# main_board.net
KiCad netlist of a schematic drawn in EAGLE
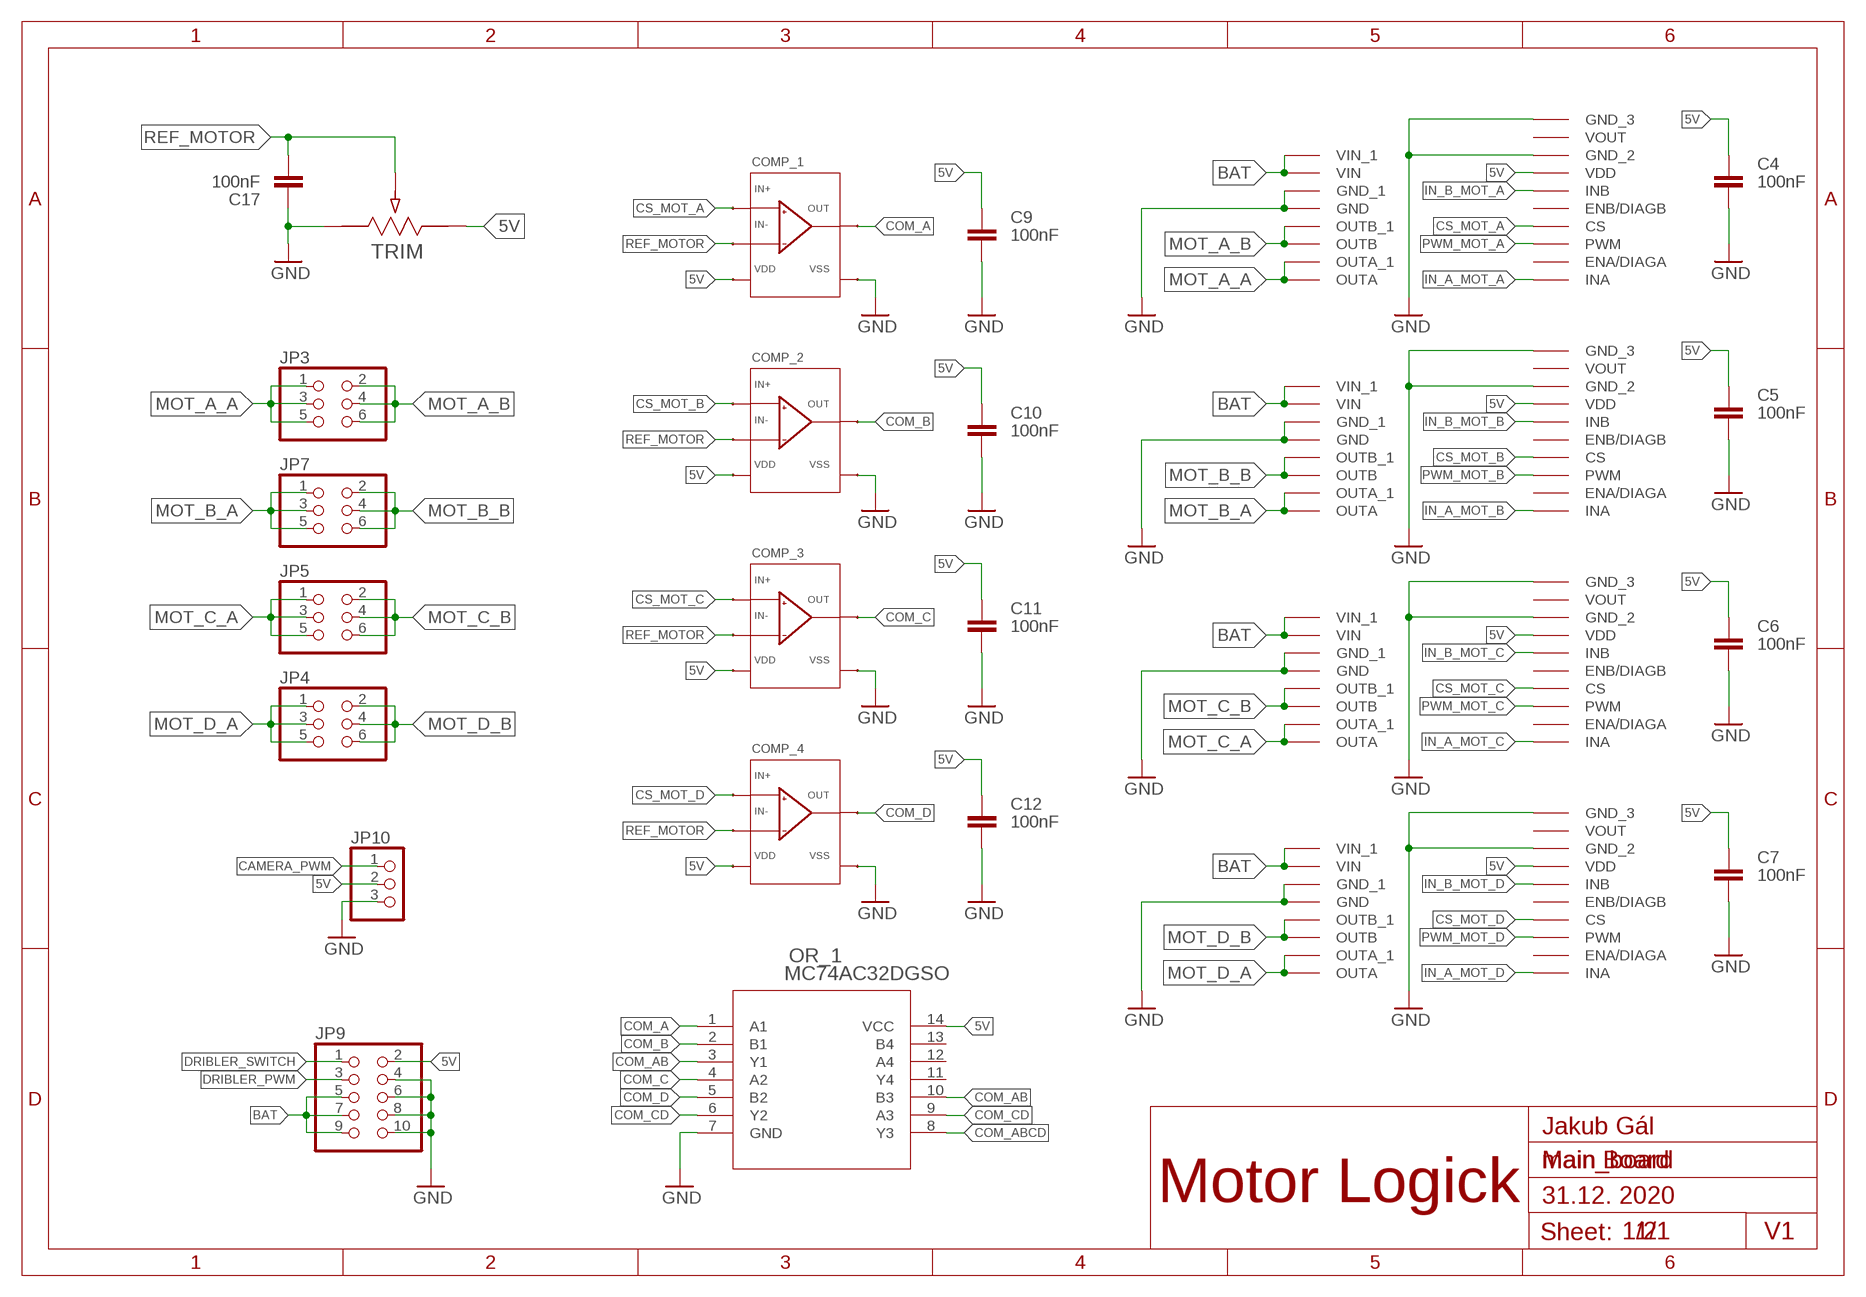
[diagram p0: schematic, sheet 1, part 1 of 2]
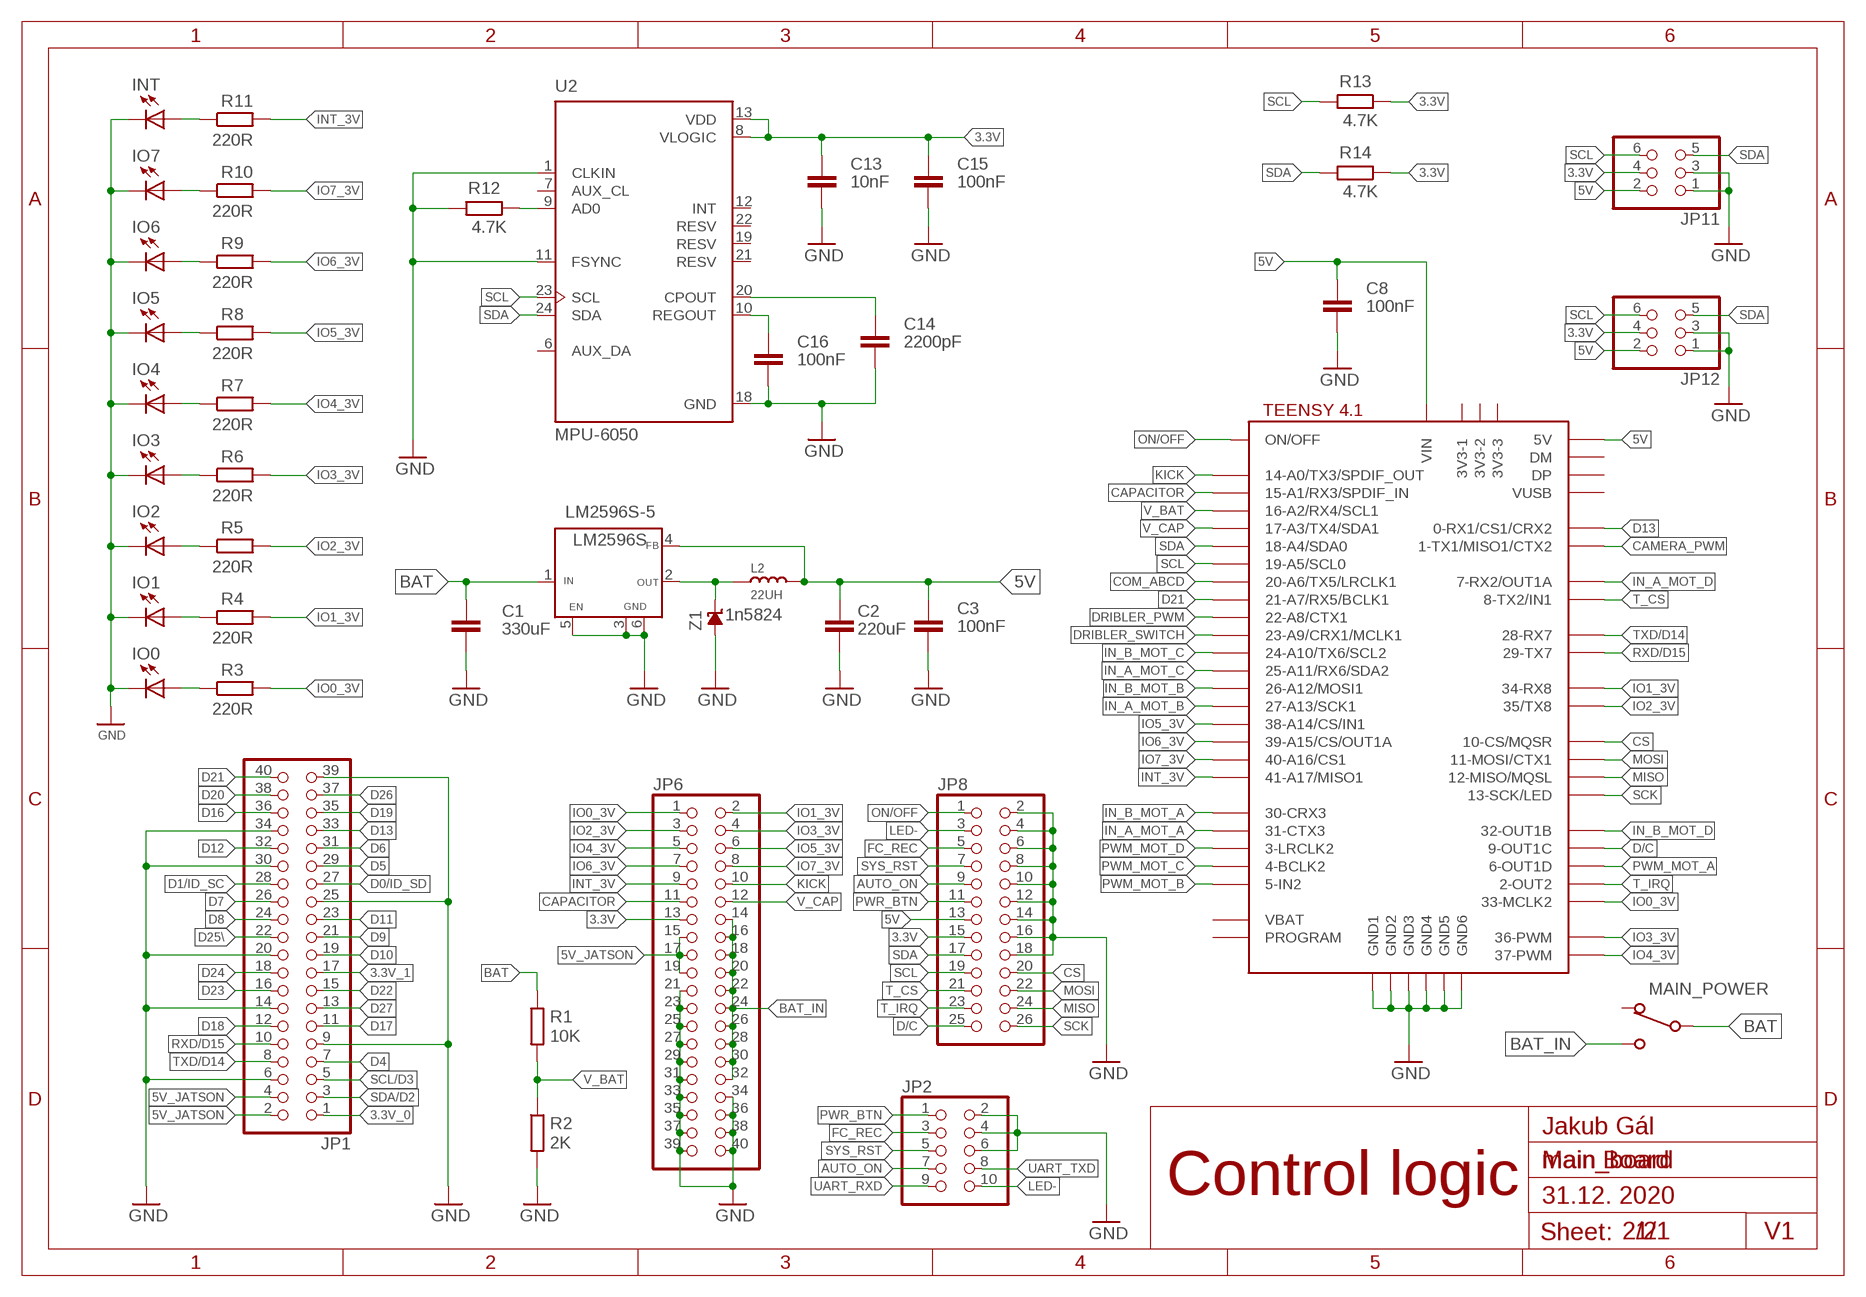
[diagram p1: schematic, sheet 1, part 2 of 2]

(export (version "E")
  (design (tool "Eeschema 10.0.6"))
  (components
    (comp (ref "C1")
      (value "330uF")
      (footprint "eagle-import:CAPM7343X310")
      (libsource (lib "eagle-import") (part "CTANTALUM-2917(7343-METRIC)_"))
    )
    (comp (ref "C2")
      (value "220uF")
      (footprint "eagle-import:CAPM7343X310")
      (libsource (lib "eagle-import") (part "CTANTALUM-2917(7343-METRIC)_"))
    )
    (comp (ref "C3")
      (value "100nF")
      (footprint "eagle-import:C0603")
      (libsource (lib "eagle-import") (part "C-EUC0603"))
    )
    (comp (ref "C4")
      (value "100nF")
      (footprint "eagle-import:C0603")
      (libsource (lib "eagle-import") (part "C-EUC0603"))
    )
    (comp (ref "C5")
      (value "100nF")
      (footprint "eagle-import:C0603")
      (libsource (lib "eagle-import") (part "C-EUC0603"))
    )
    (comp (ref "C6")
      (value "100nF")
      (footprint "eagle-import:C0603")
      (libsource (lib "eagle-import") (part "C-EUC0603"))
    )
    (comp (ref "C7")
      (value "100nF")
      (footprint "eagle-import:C0603")
      (libsource (lib "eagle-import") (part "C-EUC0603"))
    )
    (comp (ref "C8")
      (value "100nF")
      (footprint "eagle-import:C0603")
      (libsource (lib "eagle-import") (part "C-EUC0603"))
    )
    (comp (ref "C9")
      (value "100nF")
      (footprint "eagle-import:C0603")
      (libsource (lib "eagle-import") (part "C-EUC0603"))
    )
    (comp (ref "C10")
      (value "100nF")
      (footprint "eagle-import:C0603")
      (libsource (lib "eagle-import") (part "C-EUC0603"))
    )
    (comp (ref "C11")
      (value "100nF")
      (footprint "eagle-import:C0603")
      (libsource (lib "eagle-import") (part "C-EUC0603"))
    )
    (comp (ref "C12")
      (value "100nF")
      (footprint "eagle-import:C0603")
      (libsource (lib "eagle-import") (part "C-EUC0603"))
    )
    (comp (ref "C13")
      (value "10nF")
      (footprint "eagle-import:C0603")
      (libsource (lib "eagle-import") (part "C-EUC0603"))
    )
    (comp (ref "C14")
      (value "2200pF")
      (footprint "eagle-import:C0603")
      (libsource (lib "eagle-import") (part "C-EUC0603"))
    )
    (comp (ref "C15")
      (value "100nF")
      (footprint "eagle-import:C0603")
      (libsource (lib "eagle-import") (part "C-EUC0603"))
    )
    (comp (ref "C16")
      (value "100nF")
      (footprint "eagle-import:C0603")
      (libsource (lib "eagle-import") (part "C-EUC0603"))
    )
    (comp (ref "C17")
      (value "100nF")
      (footprint "eagle-import:C0603")
      (libsource (lib "eagle-import") (part "C-EUC0603"))
    )
    (comp (ref "COMP_1")
      (value "TC75S56FUTE85LF")
      (footprint "eagle-import:SOT-353___(USV)_TOS")
      (libsource (lib "eagle-import") (part "TC75S56FUTE85LF"))
    )
    (comp (ref "COMP_2")
      (value "TC75S56FUTE85LF")
      (footprint "eagle-import:SOT-353___(USV)_TOS")
      (libsource (lib "eagle-import") (part "TC75S56FUTE85LF"))
    )
    (comp (ref "COMP_3")
      (value "TC75S56FUTE85LF")
      (footprint "eagle-import:SOT-353___(USV)_TOS")
      (libsource (lib "eagle-import") (part "TC75S56FUTE85LF"))
    )
    (comp (ref "COMP_4")
      (value "TC75S56FUTE85LF")
      (footprint "eagle-import:SOT-353___(USV)_TOS")
      (libsource (lib "eagle-import") (part "TC75S56FUTE85LF"))
    )
    (comp (ref "DRIVER_A")
      (value "MOTOR_DRIVER")
      (footprint "eagle-import:MOTOR_DRIVER")
      (libsource (lib "eagle-import") (part "MOTOR_DRIVER"))
    )
    (comp (ref "DRIVER_B")
      (value "MOTOR_DRIVER")
      (footprint "eagle-import:MOTOR_DRIVER")
      (libsource (lib "eagle-import") (part "MOTOR_DRIVER"))
    )
    (comp (ref "DRIVER_C")
      (value "MOTOR_DRIVER")
      (footprint "eagle-import:MOTOR_DRIVER")
      (libsource (lib "eagle-import") (part "MOTOR_DRIVER"))
    )
    (comp (ref "DRIVER_D")
      (value "MOTOR_DRIVER")
      (footprint "eagle-import:MOTOR_DRIVER")
      (libsource (lib "eagle-import") (part "MOTOR_DRIVER"))
    )
    (comp (ref "INT")
      (value "LEDCHIPLED_0603")
      (footprint "eagle-import:CHIPLED_0603")
      (libsource (lib "eagle-import") (part "LEDCHIPLED_0603"))
    )
    (comp (ref "IO0")
      (value "LEDCHIPLED_0603")
      (footprint "eagle-import:CHIPLED_0603")
      (libsource (lib "eagle-import") (part "LEDCHIPLED_0603"))
    )
    (comp (ref "IO1")
      (value "LEDCHIPLED_0603")
      (footprint "eagle-import:CHIPLED_0603")
      (libsource (lib "eagle-import") (part "LEDCHIPLED_0603"))
    )
    (comp (ref "IO2")
      (value "LEDCHIPLED_0603")
      (footprint "eagle-import:CHIPLED_0603")
      (libsource (lib "eagle-import") (part "LEDCHIPLED_0603"))
    )
    (comp (ref "IO3")
      (value "LEDCHIPLED_0603")
      (footprint "eagle-import:CHIPLED_0603")
      (libsource (lib "eagle-import") (part "LEDCHIPLED_0603"))
    )
    (comp (ref "IO4")
      (value "LEDCHIPLED_0603")
      (footprint "eagle-import:CHIPLED_0603")
      (libsource (lib "eagle-import") (part "LEDCHIPLED_0603"))
    )
    (comp (ref "IO5")
      (value "LEDCHIPLED_0603")
      (footprint "eagle-import:CHIPLED_0603")
      (libsource (lib "eagle-import") (part "LEDCHIPLED_0603"))
    )
    (comp (ref "IO6")
      (value "LEDCHIPLED_0603")
      (footprint "eagle-import:CHIPLED_0603")
      (libsource (lib "eagle-import") (part "LEDCHIPLED_0603"))
    )
    (comp (ref "IO7")
      (value "LEDCHIPLED_0603")
      (footprint "eagle-import:CHIPLED_0603")
      (libsource (lib "eagle-import") (part "LEDCHIPLED_0603"))
    )
    (comp (ref "JP1")
      (value "PINHD-2X20_2.54-SMD")
      (footprint "eagle-import:2X20SMD")
      (libsource (lib "eagle-import") (part "PINHD-2X20_2.54-SMD"))
    )
    (comp (ref "JP2")
      (value "PINHD-2X5_2.54")
      (footprint "eagle-import:2X05")
      (libsource (lib "eagle-import") (part "PINHD-2X5_2.54"))
    )
    (comp (ref "JP3")
      (value "PINHD-2X3IDC")
      (footprint "eagle-import:2X03_IDC")
      (libsource (lib "eagle-import") (part "PINHD-2X3IDC"))
    )
    (comp (ref "JP4")
      (value "PINHD-2X3IDC")
      (footprint "eagle-import:2X03_IDC")
      (libsource (lib "eagle-import") (part "PINHD-2X3IDC"))
    )
    (comp (ref "JP5")
      (value "PINHD-2X3IDC")
      (footprint "eagle-import:2X03_IDC")
      (libsource (lib "eagle-import") (part "PINHD-2X3IDC"))
    )
    (comp (ref "JP6")
      (value "PINHD-2X20_2.54")
      (footprint "eagle-import:2X20")
      (libsource (lib "eagle-import") (part "PINHD-2X20_2.54"))
    )
    (comp (ref "JP7")
      (value "PINHD-2X3IDC")
      (footprint "eagle-import:2X03_IDC")
      (libsource (lib "eagle-import") (part "PINHD-2X3IDC"))
    )
    (comp (ref "JP8")
      (value "PINHD-2X13_2.54")
      (footprint "eagle-import:2X13")
      (libsource (lib "eagle-import") (part "PINHD-2X13_2.54"))
    )
    (comp (ref "JP9")
      (value "PINHD-2X5_2.54")
      (footprint "eagle-import:2X05")
      (libsource (lib "eagle-import") (part "PINHD-2X5_2.54"))
    )
    (comp (ref "JP10")
      (value "PINHD-1X3")
      (footprint "eagle-import:1X03")
      (libsource (lib "eagle-import") (part "PINHD-1X3"))
    )
    (comp (ref "JP11")
      (value "PINHD-2X3IDC")
      (footprint "eagle-import:2X03_IDC")
      (libsource (lib "eagle-import") (part "PINHD-2X3IDC"))
    )
    (comp (ref "JP12")
      (value "PINHD-2X3IDC")
      (footprint "eagle-import:2X03_IDC")
      (libsource (lib "eagle-import") (part "PINHD-2X3IDC"))
    )
    (comp (ref "L2")
      (value "22UH")
      (footprint "eagle-import:INDUCTOR_L0630")
      (libsource (lib "eagle-import") (part "INDUCTOR/FERRITE-BEAD0630"))
    )
    (comp (ref "LM2596S")
      (value "LM2596S-5")
      (footprint "eagle-import:TO263-5")
      (libsource (lib "eagle-import") (part "LM2596S"))
    )
    (comp (ref "MAIN_POWER")
      (value "PREP-1PB")
      (footprint "eagle-import:P-B069B")
      (libsource (lib "eagle-import") (part "PREP-1PB"))
    )
    (comp (ref "OR_1")
      (value "MC74AC32DGSO")
      (footprint "eagle-import:SOIC-14_NB_ONS-M")
      (fields
        (field (name "MANUFACTURER_PART_NUMBER") "MC74VHC32DR2G")
        (field (name "COPYRIGHT") "Copyright (C) 2016 Accelerated Designs. All rights reserved")
      )
      (libsource (lib "eagle-import") (part "MC74AC32DGSOIC-14_NB_ONS-M"))
    )
    (comp (ref "R1")
      (value "10K")
      (footprint "eagle-import:R0603")
      (libsource (lib "eagle-import") (part "R-EU_R0603"))
    )
    (comp (ref "R2")
      (value "2K")
      (footprint "eagle-import:R0603")
      (libsource (lib "eagle-import") (part "R-EU_R0603"))
    )
    (comp (ref "R3")
      (value "220R")
      (footprint "eagle-import:R0603")
      (libsource (lib "eagle-import") (part "R-EU_R0603"))
    )
    (comp (ref "R4")
      (value "220R")
      (footprint "eagle-import:R0603")
      (libsource (lib "eagle-import") (part "R-EU_R0603"))
    )
    (comp (ref "R5")
      (value "220R")
      (footprint "eagle-import:R0603")
      (libsource (lib "eagle-import") (part "R-EU_R0603"))
    )
    (comp (ref "R6")
      (value "220R")
      (footprint "eagle-import:R0603")
      (libsource (lib "eagle-import") (part "R-EU_R0603"))
    )
    (comp (ref "R7")
      (value "220R")
      (footprint "eagle-import:R0603")
      (libsource (lib "eagle-import") (part "R-EU_R0603"))
    )
    (comp (ref "R8")
      (value "220R")
      (footprint "eagle-import:R0603")
      (libsource (lib "eagle-import") (part "R-EU_R0603"))
    )
    (comp (ref "R9")
      (value "220R")
      (footprint "eagle-import:R0603")
      (libsource (lib "eagle-import") (part "R-EU_R0603"))
    )
    (comp (ref "R10")
      (value "220R")
      (footprint "eagle-import:R0603")
      (libsource (lib "eagle-import") (part "R-EU_R0603"))
    )
    (comp (ref "R11")
      (value "220R")
      (footprint "eagle-import:R0603")
      (libsource (lib "eagle-import") (part "R-EU_R0603"))
    )
    (comp (ref "R12")
      (value "4.7K")
      (footprint "eagle-import:R0603")
      (libsource (lib "eagle-import") (part "R-EU_R0603"))
    )
    (comp (ref "R13")
      (value "4.7K")
      (footprint "eagle-import:R0603")
      (libsource (lib "eagle-import") (part "R-EU_R0603"))
    )
    (comp (ref "R14")
      (value "4.7K")
      (footprint "eagle-import:R0603")
      (libsource (lib "eagle-import") (part "R-EU_R0603"))
    )
    (comp (ref "TEENSY41")
      (value "TEENSY41-E")
      (footprint "eagle-import:TENNSY41-E")
      (libsource (lib "eagle-import") (part "TEENSY41-E"))
    )
    (comp (ref "TRIM")
      (value "3362W-1-103LF")
      (footprint "eagle-import:POT_3362W")
      (libsource (lib "eagle-import") (part "3362W-1-103LF"))
    )
    (comp (ref "U2")
      (value "MPU-6050")
      (footprint "eagle-import:QFN50P400X400X95-24N")
      (fields (field (name "MF") "TDK InvenSense"))
      (libsource (lib "eagle-import") (part "MPU-6050"))
    )
    (comp (ref "Z1")
      (value "1n5824")
      (footprint "eagle-import:SUPRESSOR_SMAJ")
      (libsource (lib "eagle-import") (part "SUPRESSOR_TVS-UD-SMAJ"))
    )
  )
  (nets
    (net (code "1") (name "3.3V") (class "Default")
      (node (ref "C13") (pin "1") (pinfunction "1_1") (pintype "passive"))
      (node (ref "C15") (pin "1") (pinfunction "1_1") (pintype "passive"))
      (node (ref "JP11") (pin "4") (pinfunction "4_4") (pintype "passive"))
      (node (ref "JP12") (pin "4") (pinfunction "4_4") (pintype "passive"))
      (node (ref "JP6") (pin "13") (pinfunction "13_13") (pintype "passive"))
      (node (ref "JP8") (pin "15") (pinfunction "15_15") (pintype "passive"))
      (node (ref "R13") (pin "1") (pinfunction "1_1") (pintype "passive"))
      (node (ref "R14") (pin "1") (pinfunction "1_1") (pintype "passive"))
      (node (ref "U2") (pin "13") (pinfunction "VDD_13") (pintype "power_in"))
      (node (ref "U2") (pin "8") (pinfunction "VLOGIC_8") (pintype "power_in"))
    )
    (net (code "2") (name "3.3V_0") (class "Default")
      (node (ref "JP1") (pin "1") (pinfunction "1_1") (pintype "passive"))
    )
    (net (code "3") (name "3.3V_1") (class "Default")
      (node (ref "JP1") (pin "17") (pinfunction "17_17") (pintype "passive"))
    )
    (net (code "4") (name "5V") (class "Default")
      (node (ref "C10") (pin "1") (pinfunction "1_1") (pintype "passive"))
      (node (ref "C11") (pin "1") (pinfunction "1_1") (pintype "passive"))
      (node (ref "C12") (pin "1") (pinfunction "1_1") (pintype "passive"))
      (node (ref "C2") (pin "1") (pinfunction "1_1") (pintype "passive"))
      (node (ref "C3") (pin "1") (pinfunction "1_1") (pintype "passive"))
      (node (ref "C4") (pin "1") (pinfunction "1_1") (pintype "passive"))
      (node (ref "C5") (pin "1") (pinfunction "1_1") (pintype "passive"))
      (node (ref "C6") (pin "1") (pinfunction "1_1") (pintype "passive"))
      (node (ref "C7") (pin "1") (pinfunction "1_1") (pintype "passive"))
      (node (ref "C8") (pin "1") (pinfunction "1_1") (pintype "passive"))
      (node (ref "C9") (pin "1") (pinfunction "1_1") (pintype "passive"))
      (node (ref "COMP_1") (pin "5") (pinfunction "5_5") (pintype "passive"))
      (node (ref "COMP_2") (pin "5") (pinfunction "5_5") (pintype "passive"))
      (node (ref "COMP_3") (pin "5") (pinfunction "5_5") (pintype "passive"))
      (node (ref "COMP_4") (pin "5") (pinfunction "5_5") (pintype "passive"))
      (node (ref "DRIVER_A") (pin "VDD") (pinfunction "VDD_VDD") (pintype "bidirectional"))
      (node (ref "DRIVER_B") (pin "VDD") (pinfunction "VDD_VDD") (pintype "bidirectional"))
      (node (ref "DRIVER_C") (pin "VDD") (pinfunction "VDD_VDD") (pintype "bidirectional"))
      (node (ref "DRIVER_D") (pin "VDD") (pinfunction "VDD_VDD") (pintype "bidirectional"))
      (node (ref "JP10") (pin "2") (pinfunction "2_2") (pintype "passive"))
      (node (ref "JP11") (pin "2") (pinfunction "2_2") (pintype "passive"))
      (node (ref "JP12") (pin "2") (pinfunction "2_2") (pintype "passive"))
      (node (ref "JP8") (pin "13") (pinfunction "13_13") (pintype "passive"))
      (node (ref "JP9") (pin "2") (pinfunction "2_2") (pintype "passive"))
      (node (ref "L2") (pin "2") (pinfunction "2_2") (pintype "passive"))
      (node (ref "LM2596S") (pin "4") (pinfunction "FB_4") (pintype "input"))
      (node (ref "OR_1") (pin "14") (pinfunction "VCC_14") (pintype "power_in"))
      (node (ref "TEENSY41") (pin "+5V") (pinfunction "5V_+5V") (pintype "bidirectional"))
      (node (ref "TEENSY41") (pin "VIN") (pinfunction "VIN_VIN") (pintype "bidirectional"))
      (node (ref "TRIM") (pin "3") (pinfunction "3_3") (pintype "passive"))
    )
    (net (code "5") (name "5V_JATSON") (class "Default")
      (node (ref "JP1") (pin "2") (pinfunction "2_2") (pintype "passive"))
      (node (ref "JP1") (pin "4") (pinfunction "4_4") (pintype "passive"))
      (node (ref "JP6") (pin "15") (pinfunction "15_15") (pintype "passive"))
      (node (ref "JP6") (pin "17") (pinfunction "17_17") (pintype "passive"))
      (node (ref "JP6") (pin "19") (pinfunction "19_19") (pintype "passive"))
    )
    (net (code "6") (name "AUTO_ON") (class "Default")
      (node (ref "JP2") (pin "7") (pinfunction "7_7") (pintype "passive"))
      (node (ref "JP8") (pin "9") (pinfunction "9_9") (pintype "passive"))
    )
    (net (code "7") (name "BAT") (class "Default")
      (node (ref "C1") (pin "1") (pinfunction "1_1") (pintype "passive"))
      (node (ref "DRIVER_A") (pin "VIN") (pinfunction "VIN_VIN") (pintype "bidirectional"))
      (node (ref "DRIVER_A") (pin "VIN_1") (pinfunction "VIN_1_VIN_1") (pintype "bidirectional"))
      (node (ref "DRIVER_B") (pin "VIN") (pinfunction "VIN_VIN") (pintype "bidirectional"))
      (node (ref "DRIVER_B") (pin "VIN_1") (pinfunction "VIN_1_VIN_1") (pintype "bidirectional"))
      (node (ref "DRIVER_C") (pin "VIN") (pinfunction "VIN_VIN") (pintype "bidirectional"))
      (node (ref "DRIVER_C") (pin "VIN_1") (pinfunction "VIN_1_VIN_1") (pintype "bidirectional"))
      (node (ref "DRIVER_D") (pin "VIN") (pinfunction "VIN_VIN") (pintype "bidirectional"))
      (node (ref "DRIVER_D") (pin "VIN_1") (pinfunction "VIN_1_VIN_1") (pintype "bidirectional"))
      (node (ref "JP9") (pin "5") (pinfunction "5_5") (pintype "passive"))
      (node (ref "JP9") (pin "7") (pinfunction "7_7") (pintype "passive"))
      (node (ref "JP9") (pin "9") (pinfunction "9_9") (pintype "passive"))
      (node (ref "LM2596S") (pin "1") (pinfunction "IN_1") (pintype "input"))
      (node (ref "MAIN_POWER") (pin "2") (pinfunction "2-COM_2") (pintype "passive"))
      (node (ref "R1") (pin "1") (pinfunction "1_1") (pintype "passive"))
    )
    (net (code "8") (name "BAT_IN") (class "Default")
      (node (ref "JP6") (pin "14") (pinfunction "14_14") (pintype "passive"))
      (node (ref "JP6") (pin "16") (pinfunction "16_16") (pintype "passive"))
      (node (ref "JP6") (pin "18") (pinfunction "18_18") (pintype "passive"))
      (node (ref "JP6") (pin "20") (pinfunction "20_20") (pintype "passive"))
      (node (ref "JP6") (pin "22") (pinfunction "22_22") (pintype "passive"))
      (node (ref "JP6") (pin "24") (pinfunction "24_24") (pintype "passive"))
      (node (ref "JP6") (pin "26") (pinfunction "26_26") (pintype "passive"))
      (node (ref "JP6") (pin "28") (pinfunction "28_28") (pintype "passive"))
      (node (ref "JP6") (pin "30") (pinfunction "30_30") (pintype "passive"))
      (node (ref "JP6") (pin "32") (pinfunction "32_32") (pintype "passive"))
      (node (ref "MAIN_POWER") (pin "1") (pinfunction "1-OFF_1") (pintype "passive"))
    )
    (net (code "9") (name "CAMERA_PWM") (class "Default")
      (node (ref "JP10") (pin "1") (pinfunction "1_1") (pintype "passive"))
      (node (ref "TEENSY41") (pin "1-TX1/MISO1/CTX2") (pinfunction "1-TX1/MISO1/CTX2_1-TX1/MISO1/CTX2") (pintype "bidirectional"))
    )
    (net (code "10") (name "CAPACITOR") (class "Default")
      (node (ref "JP6") (pin "11") (pinfunction "11_11") (pintype "passive"))
      (node (ref "TEENSY41") (pin "15-A1/RX3/SPDIF_IN") (pinfunction "15-A1/RX3/SPDIF_IN_15-A1/RX3/SPDIF_IN") (pintype "bidirectional"))
    )
    (net (code "11") (name "COM_A") (class "Default")
      (node (ref "COMP_1") (pin "4") (pinfunction "4_4") (pintype "passive"))
      (node (ref "OR_1") (pin "1") (pinfunction "A1_1") (pintype "input"))
    )
    (net (code "12") (name "COM_AB") (class "Default")
      (node (ref "OR_1") (pin "10") (pinfunction "B3_10") (pintype "input"))
      (node (ref "OR_1") (pin "3") (pinfunction "Y1_3") (pintype "output"))
    )
    (net (code "13") (name "COM_ABCD") (class "Default")
      (node (ref "OR_1") (pin "8") (pinfunction "Y3_8") (pintype "output"))
      (node (ref "TEENSY41") (pin "20-A6/TX5/LRCLK1") (pinfunction "20-A6/TX5/LRCLK1_20-A6/TX5/LRCLK1") (pintype "bidirectional"))
    )
    (net (code "14") (name "COM_B") (class "Default")
      (node (ref "COMP_2") (pin "4") (pinfunction "4_4") (pintype "passive"))
      (node (ref "OR_1") (pin "2") (pinfunction "B1_2") (pintype "input"))
    )
    (net (code "15") (name "COM_C") (class "Default")
      (node (ref "COMP_3") (pin "4") (pinfunction "4_4") (pintype "passive"))
      (node (ref "OR_1") (pin "4") (pinfunction "A2_4") (pintype "input"))
    )
    (net (code "16") (name "COM_CD") (class "Default")
      (node (ref "OR_1") (pin "6") (pinfunction "Y2_6") (pintype "output"))
      (node (ref "OR_1") (pin "9") (pinfunction "A3_9") (pintype "input"))
    )
    (net (code "17") (name "COM_D") (class "Default")
      (node (ref "COMP_4") (pin "4") (pinfunction "4_4") (pintype "passive"))
      (node (ref "OR_1") (pin "5") (pinfunction "B2_5") (pintype "input"))
    )
    (net (code "18") (name "CS") (class "Default")
      (node (ref "JP8") (pin "20") (pinfunction "20_20") (pintype "passive"))
      (node (ref "TEENSY41") (pin "10-CS\\MQSR") (pinfunction "10-CS/MQSR_10-CS\\MQSR") (pintype "bidirectional"))
    )
    (net (code "19") (name "CS_MOT_A") (class "Default")
      (node (ref "COMP_1") (pin "3") (pinfunction "3_3") (pintype "passive"))
      (node (ref "DRIVER_A") (pin "CS") (pinfunction "CS_CS") (pintype "bidirectional"))
    )
    (net (code "20") (name "CS_MOT_B") (class "Default")
      (node (ref "COMP_2") (pin "3") (pinfunction "3_3") (pintype "passive"))
      (node (ref "DRIVER_B") (pin "CS") (pinfunction "CS_CS") (pintype "bidirectional"))
    )
    (net (code "21") (name "CS_MOT_C") (class "Default")
      (node (ref "COMP_3") (pin "3") (pinfunction "3_3") (pintype "passive"))
      (node (ref "DRIVER_C") (pin "CS") (pinfunction "CS_CS") (pintype "bidirectional"))
    )
    (net (code "22") (name "CS_MOT_D") (class "Default")
      (node (ref "COMP_4") (pin "3") (pinfunction "3_3") (pintype "passive"))
      (node (ref "DRIVER_D") (pin "CS") (pinfunction "CS_CS") (pintype "bidirectional"))
    )
    (net (code "23") (name "D0{slash}ID_SD") (class "Default")
      (node (ref "JP1") (pin "27") (pinfunction "27_27") (pintype "passive"))
    )
    (net (code "24") (name "D1{slash}ID_SC") (class "Default")
      (node (ref "JP1") (pin "28") (pinfunction "28_28") (pintype "passive"))
    )
    (net (code "25") (name "D4") (class "Default")
      (node (ref "JP1") (pin "7") (pinfunction "7_7") (pintype "passive"))
    )
    (net (code "26") (name "D5") (class "Default")
      (node (ref "JP1") (pin "29") (pinfunction "29_29") (pintype "passive"))
    )
    (net (code "27") (name "D6") (class "Default")
      (node (ref "JP1") (pin "31") (pinfunction "31_31") (pintype "passive"))
    )
    (net (code "28") (name "D7") (class "Default")
      (node (ref "JP1") (pin "26") (pinfunction "26_26") (pintype "passive"))
    )
    (net (code "29") (name "D8") (class "Default")
      (node (ref "JP1") (pin "24") (pinfunction "24_24") (pintype "passive"))
    )
    (net (code "30") (name "D9") (class "Default")
      (node (ref "JP1") (pin "21") (pinfunction "21_21") (pintype "passive"))
    )
    (net (code "31") (name "D10") (class "Default")
      (node (ref "JP1") (pin "19") (pinfunction "19_19") (pintype "passive"))
    )
    (net (code "32") (name "D11") (class "Default")
      (node (ref "JP1") (pin "23") (pinfunction "23_23") (pintype "passive"))
    )
    (net (code "33") (name "D12") (class "Default")
      (node (ref "JP1") (pin "32") (pinfunction "32_32") (pintype "passive"))
    )
    (net (code "34") (name "D13") (class "Default")
      (node (ref "JP1") (pin "33") (pinfunction "33_33") (pintype "passive"))
      (node (ref "TEENSY41") (pin "0-RX1/CS1/CRX2") (pinfunction "0-RX1/CS1/CRX2_0-RX1/CS1/CRX2") (pintype "bidirectional"))
    )
    (net (code "35") (name "D16") (class "Default")
      (node (ref "JP1") (pin "36") (pinfunction "36_36") (pintype "passive"))
    )
    (net (code "36") (name "D17") (class "Default")
      (node (ref "JP1") (pin "11") (pinfunction "11_11") (pintype "passive"))
    )
    (net (code "37") (name "D18") (class "Default")
      (node (ref "JP1") (pin "12") (pinfunction "12_12") (pintype "passive"))
    )
    (net (code "38") (name "D19") (class "Default")
      (node (ref "JP1") (pin "35") (pinfunction "35_35") (pintype "passive"))
    )
    (net (code "39") (name "D20") (class "Default")
      (node (ref "JP1") (pin "38") (pinfunction "38_38") (pintype "passive"))
    )
    (net (code "40") (name "D21") (class "Default")
      (node (ref "JP1") (pin "40") (pinfunction "40_40") (pintype "passive"))
      (node (ref "TEENSY41") (pin "21-A7/RX5/BCLK1") (pinfunction "21-A7/RX5/BCLK1_21-A7/RX5/BCLK1") (pintype "bidirectional"))
    )
    (net (code "41") (name "D22") (class "Default")
      (node (ref "JP1") (pin "15") (pinfunction "15_15") (pintype "passive"))
    )
    (net (code "42") (name "D23") (class "Default")
      (node (ref "JP1") (pin "16") (pinfunction "16_16") (pintype "passive"))
    )
    (net (code "43") (name "D24") (class "Default")
      (node (ref "JP1") (pin "18") (pinfunction "18_18") (pintype "passive"))
    )
    (net (code "44") (name "D25\\") (class "Default")
      (node (ref "JP1") (pin "22") (pinfunction "22_22") (pintype "passive"))
    )
    (net (code "45") (name "D26") (class "Default")
      (node (ref "JP1") (pin "37") (pinfunction "37_37") (pintype "passive"))
    )
    (net (code "46") (name "D27") (class "Default")
      (node (ref "JP1") (pin "13") (pinfunction "13_13") (pintype "passive"))
    )
    (net (code "47") (name "DRIBLER_PWM") (class "Default")
      (node (ref "JP9") (pin "3") (pinfunction "3_3") (pintype "passive"))
      (node (ref "TEENSY41") (pin "22-A8/CTX1") (pinfunction "22-A8/CTX1_22-A8/CTX1") (pintype "bidirectional"))
    )
    (net (code "48") (name "DRIBLER_SWITCH") (class "Default")
      (node (ref "JP9") (pin "1") (pinfunction "1_1") (pintype "passive"))
      (node (ref "TEENSY41") (pin "23-A9/CRX1/MCLK1") (pinfunction "23-A9/CRX1/MCLK1_23-A9/CRX1/MCLK1") (pintype "bidirectional"))
    )
    (net (code "49") (name "D{slash}C") (class "Default")
      (node (ref "JP8") (pin "25") (pinfunction "25_25") (pintype "passive"))
      (node (ref "TEENSY41") (pin "9-OUT1C") (pinfunction "9-OUT1C_9-OUT1C") (pintype "bidirectional"))
    )
    (net (code "50") (name "FC_REC") (class "Default")
      (node (ref "JP2") (pin "3") (pinfunction "3_3") (pintype "passive"))
      (node (ref "JP8") (pin "5") (pinfunction "5_5") (pintype "passive"))
    )
    (net (code "51") (name "GND") (class "Default")
      (node (ref "C1") (pin "2") (pinfunction "2_2") (pintype "passive"))
      (node (ref "C10") (pin "2") (pinfunction "2_2") (pintype "passive"))
      (node (ref "C11") (pin "2") (pinfunction "2_2") (pintype "passive"))
      (node (ref "C12") (pin "2") (pinfunction "2_2") (pintype "passive"))
      (node (ref "C13") (pin "2") (pinfunction "2_2") (pintype "passive"))
      (node (ref "C14") (pin "2") (pinfunction "2_2") (pintype "passive"))
      (node (ref "C15") (pin "2") (pinfunction "2_2") (pintype "passive"))
      (node (ref "C16") (pin "2") (pinfunction "2_2") (pintype "passive"))
      (node (ref "C17") (pin "1") (pinfunction "1_1") (pintype "passive"))
      (node (ref "C2") (pin "2") (pinfunction "2_2") (pintype "passive"))
      (node (ref "C3") (pin "2") (pinfunction "2_2") (pintype "passive"))
      (node (ref "C4") (pin "2") (pinfunction "2_2") (pintype "passive"))
      (node (ref "C5") (pin "2") (pinfunction "2_2") (pintype "passive"))
      (node (ref "C6") (pin "2") (pinfunction "2_2") (pintype "passive"))
      (node (ref "C7") (pin "2") (pinfunction "2_2") (pintype "passive"))
      (node (ref "C8") (pin "2") (pinfunction "2_2") (pintype "passive"))
      (node (ref "C9") (pin "2") (pinfunction "2_2") (pintype "passive"))
      (node (ref "COMP_1") (pin "2") (pinfunction "2_2") (pintype "passive"))
      (node (ref "COMP_2") (pin "2") (pinfunction "2_2") (pintype "passive"))
      (node (ref "COMP_3") (pin "2") (pinfunction "2_2") (pintype "passive"))
      (node (ref "COMP_4") (pin "2") (pinfunction "2_2") (pintype "passive"))
      (node (ref "DRIVER_A") (pin "GND") (pinfunction "GND_GND") (pintype "bidirectional"))
      (node (ref "DRIVER_A") (pin "GND_1") (pinfunction "GND_1_GND_1") (pintype "bidirectional"))
      (node (ref "DRIVER_A") (pin "GND_2") (pinfunction "GND_2_GND_2") (pintype "bidirectional"))
      (node (ref "DRIVER_A") (pin "GND_3") (pinfunction "GND_3_GND_3") (pintype "bidirectional"))
      (node (ref "DRIVER_B") (pin "GND") (pinfunction "GND_GND") (pintype "bidirectional"))
      (node (ref "DRIVER_B") (pin "GND_1") (pinfunction "GND_1_GND_1") (pintype "bidirectional"))
      (node (ref "DRIVER_B") (pin "GND_2") (pinfunction "GND_2_GND_2") (pintype "bidirectional"))
      (node (ref "DRIVER_B") (pin "GND_3") (pinfunction "GND_3_GND_3") (pintype "bidirectional"))
      (node (ref "DRIVER_C") (pin "GND") (pinfunction "GND_GND") (pintype "bidirectional"))
      (node (ref "DRIVER_C") (pin "GND_1") (pinfunction "GND_1_GND_1") (pintype "bidirectional"))
      (node (ref "DRIVER_C") (pin "GND_2") (pinfunction "GND_2_GND_2") (pintype "bidirectional"))
      (node (ref "DRIVER_C") (pin "GND_3") (pinfunction "GND_3_GND_3") (pintype "bidirectional"))
      (node (ref "DRIVER_D") (pin "GND") (pinfunction "GND_GND") (pintype "bidirectional"))
      (node (ref "DRIVER_D") (pin "GND_1") (pinfunction "GND_1_GND_1") (pintype "bidirectional"))
      (node (ref "DRIVER_D") (pin "GND_2") (pinfunction "GND_2_GND_2") (pintype "bidirectional"))
      (node (ref "DRIVER_D") (pin "GND_3") (pinfunction "GND_3_GND_3") (pintype "bidirectional"))
      (node (ref "INT") (pin "C") (pinfunction "C_C") (pintype "passive"))
      (node (ref "IO0") (pin "C") (pinfunction "C_C") (pintype "passive"))
      (node (ref "IO1") (pin "C") (pinfunction "C_C") (pintype "passive"))
      (node (ref "IO2") (pin "C") (pinfunction "C_C") (pintype "passive"))
      (node (ref "IO3") (pin "C") (pinfunction "C_C") (pintype "passive"))
      (node (ref "IO4") (pin "C") (pinfunction "C_C") (pintype "passive"))
      (node (ref "IO5") (pin "C") (pinfunction "C_C") (pintype "passive"))
      (node (ref "IO6") (pin "C") (pinfunction "C_C") (pintype "passive"))
      (node (ref "IO7") (pin "C") (pinfunction "C_C") (pintype "passive"))
      (node (ref "JP1") (pin "14") (pinfunction "14_14") (pintype "passive"))
      (node (ref "JP1") (pin "20") (pinfunction "20_20") (pintype "passive"))
      (node (ref "JP1") (pin "25") (pinfunction "25_25") (pintype "passive"))
      (node (ref "JP1") (pin "30") (pinfunction "30_30") (pintype "passive"))
      (node (ref "JP1") (pin "34") (pinfunction "34_34") (pintype "passive"))
      (node (ref "JP1") (pin "39") (pinfunction "39_39") (pintype "passive"))
      (node (ref "JP1") (pin "6") (pinfunction "6_6") (pintype "passive"))
      (node (ref "JP1") (pin "9") (pinfunction "9_9") (pintype "passive"))
      (node (ref "JP10") (pin "3") (pinfunction "3_3") (pintype "passive"))
      (node (ref "JP11") (pin "1") (pinfunction "1_1") (pintype "passive"))
      (node (ref "JP11") (pin "3") (pinfunction "3_3") (pintype "passive"))
      (node (ref "JP12") (pin "1") (pinfunction "1_1") (pintype "passive"))
      (node (ref "JP12") (pin "3") (pinfunction "3_3") (pintype "passive"))
      (node (ref "JP2") (pin "2") (pinfunction "2_2") (pintype "passive"))
      (node (ref "JP2") (pin "4") (pinfunction "4_4") (pintype "passive"))
      (node (ref "JP2") (pin "6") (pinfunction "6_6") (pintype "passive"))
      (node (ref "JP6") (pin "21") (pinfunction "21_21") (pintype "passive"))
      (node (ref "JP6") (pin "23") (pinfunction "23_23") (pintype "passive"))
      (node (ref "JP6") (pin "25") (pinfunction "25_25") (pintype "passive"))
      (node (ref "JP6") (pin "27") (pinfunction "27_27") (pintype "passive"))
      (node (ref "JP6") (pin "29") (pinfunction "29_29") (pintype "passive"))
      (node (ref "JP6") (pin "31") (pinfunction "31_31") (pintype "passive"))
      (node (ref "JP6") (pin "33") (pinfunction "33_33") (pintype "passive"))
      (node (ref "JP6") (pin "34") (pinfunction "34_34") (pintype "passive"))
      (node (ref "JP6") (pin "35") (pinfunction "35_35") (pintype "passive"))
      (node (ref "JP6") (pin "36") (pinfunction "36_36") (pintype "passive"))
      (node (ref "JP6") (pin "37") (pinfunction "37_37") (pintype "passive"))
      (node (ref "JP6") (pin "38") (pinfunction "38_38") (pintype "passive"))
      (node (ref "JP6") (pin "39") (pinfunction "39_39") (pintype "passive"))
      (node (ref "JP6") (pin "40") (pinfunction "40_40") (pintype "passive"))
      (node (ref "JP8") (pin "10") (pinfunction "10_10") (pintype "passive"))
      (node (ref "JP8") (pin "12") (pinfunction "12_12") (pintype "passive"))
      (node (ref "JP8") (pin "14") (pinfunction "14_14") (pintype "passive"))
      (node (ref "JP8") (pin "16") (pinfunction "16_16") (pintype "passive"))
      (node (ref "JP8") (pin "18") (pinfunction "18_18") (pintype "passive"))
      (node (ref "JP8") (pin "2") (pinfunction "2_2") (pintype "passive"))
      (node (ref "JP8") (pin "4") (pinfunction "4_4") (pintype "passive"))
      (node (ref "JP8") (pin "6") (pinfunction "6_6") (pintype "passive"))
      (node (ref "JP8") (pin "8") (pinfunction "8_8") (pintype "passive"))
      (node (ref "JP9") (pin "10") (pinfunction "10_10") (pintype "passive"))
      (node (ref "JP9") (pin "4") (pinfunction "4_4") (pintype "passive"))
      (node (ref "JP9") (pin "6") (pinfunction "6_6") (pintype "passive"))
      (node (ref "JP9") (pin "8") (pinfunction "8_8") (pintype "passive"))
      (node (ref "LM2596S") (pin "3") (pinfunction "GND_3") (pintype "power_in"))
      (node (ref "LM2596S") (pin "5") (pinfunction "EN_5") (pintype "input"))
      (node (ref "LM2596S") (pin "6") (pinfunction "GND_6") (pintype "power_in"))
      (node (ref "OR_1") (pin "7") (pinfunction "GND_7") (pintype "power_in"))
      (node (ref "R12") (pin "2") (pinfunction "2_2") (pintype "passive"))
      (node (ref "R2") (pin "2") (pinfunction "2_2") (pintype "passive"))
      (node (ref "TEENSY41") (pin "GND1") (pinfunction "GND1_GND1") (pintype "bidirectional"))
      (node (ref "TEENSY41") (pin "GND2") (pinfunction "GND2_GND2") (pintype "bidirectional"))
      (node (ref "TEENSY41") (pin "GND3") (pinfunction "GND3_GND3") (pintype "bidirectional"))
      (node (ref "TEENSY41") (pin "GND4") (pinfunction "GND4_GND4") (pintype "bidirectional"))
      (node (ref "TEENSY41") (pin "GND5") (pinfunction "GND5_GND5") (pintype "bidirectional"))
      (node (ref "TEENSY41") (pin "GND6") (pinfunction "GND6_GND6") (pintype "bidirectional"))
      (node (ref "TRIM") (pin "1") (pinfunction "1_1") (pintype "passive"))
      (node (ref "U2") (pin "1") (pinfunction "CLKIN_1") (pintype "input"))
      (node (ref "U2") (pin "11") (pinfunction "FSYNC_11") (pintype "input"))
      (node (ref "U2") (pin "18") (pinfunction "GND_18") (pintype "power_in"))
      (node (ref "Z1") (pin "A") (pinfunction "A_A") (pintype "passive"))
    )
    (net (code "52") (name "INT_3V") (class "Default")
      (node (ref "JP6") (pin "9") (pinfunction "9_9") (pintype "passive"))
      (node (ref "R11") (pin "2") (pinfunction "2_2") (pintype "passive"))
      (node (ref "TEENSY41") (pin "41-A17/MISO1") (pinfunction "41-A17/MISO1_41-A17/MISO1") (pintype "bidirectional"))
    )
    (net (code "53") (name "IN_A_MOT_A") (class "Default")
      (node (ref "DRIVER_A") (pin "INA") (pinfunction "INA_INA") (pintype "bidirectional"))
      (node (ref "TEENSY41") (pin "31-CTX3") (pinfunction "31-CTX3_31-CTX3") (pintype "bidirectional"))
    )
    (net (code "54") (name "IN_A_MOT_B") (class "Default")
      (node (ref "DRIVER_B") (pin "INA") (pinfunction "INA_INA") (pintype "bidirectional"))
      (node (ref "TEENSY41") (pin "27-A13/SCK1") (pinfunction "27-A13/SCK1_27-A13/SCK1") (pintype "bidirectional"))
    )
    (net (code "55") (name "IN_A_MOT_C") (class "Default")
      (node (ref "DRIVER_C") (pin "INA") (pinfunction "INA_INA") (pintype "bidirectional"))
      (node (ref "TEENSY41") (pin "25-A11/RX6/SDA2") (pinfunction "25-A11/RX6/SDA2_25-A11/RX6/SDA2") (pintype "bidirectional"))
    )
    (net (code "56") (name "IN_A_MOT_D") (class "Default")
      (node (ref "DRIVER_D") (pin "INA") (pinfunction "INA_INA") (pintype "bidirectional"))
      (node (ref "TEENSY41") (pin "7-RX2/OUT1A") (pinfunction "7-RX2/OUT1A_7-RX2/OUT1A") (pintype "bidirectional"))
    )
    (net (code "57") (name "IN_B_MOT_A") (class "Default")
      (node (ref "DRIVER_A") (pin "INB") (pinfunction "INB_INB") (pintype "bidirectional"))
      (node (ref "TEENSY41") (pin "30-CRX3") (pinfunction "30-CRX3_30-CRX3") (pintype "bidirectional"))
    )
    (net (code "58") (name "IN_B_MOT_B") (class "Default")
      (node (ref "DRIVER_B") (pin "INB") (pinfunction "INB_INB") (pintype "bidirectional"))
      (node (ref "TEENSY41") (pin "26-A12/MOSI1") (pinfunction "26-A12/MOSI1_26-A12/MOSI1") (pintype "bidirectional"))
    )
    (net (code "59") (name "IN_B_MOT_C") (class "Default")
      (node (ref "DRIVER_C") (pin "INB") (pinfunction "INB_INB") (pintype "bidirectional"))
      (node (ref "TEENSY41") (pin "24-A10/TX6/SCL2") (pinfunction "24-A10/TX6/SCL2_24-A10/TX6/SCL2") (pintype "bidirectional"))
    )
    (net (code "60") (name "IN_B_MOT_D") (class "Default")
      (node (ref "DRIVER_D") (pin "INB") (pinfunction "INB_INB") (pintype "bidirectional"))
      (node (ref "TEENSY41") (pin "32-OUT1B") (pinfunction "32-OUT1B_32-OUT1B") (pintype "bidirectional"))
    )
    (net (code "61") (name "IO0_3V") (class "Default")
      (node (ref "JP6") (pin "1") (pinfunction "1_1") (pintype "passive"))
      (node (ref "R3") (pin "2") (pinfunction "2_2") (pintype "passive"))
      (node (ref "TEENSY41") (pin "33-MCLK2") (pinfunction "33-MCLK2_33-MCLK2") (pintype "bidirectional"))
    )
    (net (code "62") (name "IO1_3V") (class "Default")
      (node (ref "JP6") (pin "2") (pinfunction "2_2") (pintype "passive"))
      (node (ref "R4") (pin "2") (pinfunction "2_2") (pintype "passive"))
      (node (ref "TEENSY41") (pin "34-RX8") (pinfunction "34-RX8_34-RX8") (pintype "bidirectional"))
    )
    (net (code "63") (name "IO2_3V") (class "Default")
      (node (ref "JP6") (pin "3") (pinfunction "3_3") (pintype "passive"))
      (node (ref "R5") (pin "2") (pinfunction "2_2") (pintype "passive"))
      (node (ref "TEENSY41") (pin "35-TX8") (pinfunction "35/TX8_35-TX8") (pintype "bidirectional"))
    )
    (net (code "64") (name "IO3_3V") (class "Default")
      (node (ref "JP6") (pin "4") (pinfunction "4_4") (pintype "passive"))
      (node (ref "R6") (pin "2") (pinfunction "2_2") (pintype "passive"))
      (node (ref "TEENSY41") (pin "36-PWM") (pinfunction "36-PWM_36-PWM") (pintype "bidirectional"))
    )
    (net (code "65") (name "IO4_3V") (class "Default")
      (node (ref "JP6") (pin "5") (pinfunction "5_5") (pintype "passive"))
      (node (ref "R7") (pin "2") (pinfunction "2_2") (pintype "passive"))
      (node (ref "TEENSY41") (pin "37-PWM") (pinfunction "37-PWM_37-PWM") (pintype "bidirectional"))
    )
    (net (code "66") (name "IO5_3V") (class "Default")
      (node (ref "JP6") (pin "6") (pinfunction "6_6") (pintype "passive"))
      (node (ref "R8") (pin "2") (pinfunction "2_2") (pintype "passive"))
      (node (ref "TEENSY41") (pin "38-A14/CS/IN1") (pinfunction "38-A14/CS/IN1_38-A14/CS/IN1") (pintype "bidirectional"))
    )
    (net (code "67") (name "IO6_3V") (class "Default")
      (node (ref "JP6") (pin "7") (pinfunction "7_7") (pintype "passive"))
      (node (ref "R9") (pin "2") (pinfunction "2_2") (pintype "passive"))
      (node (ref "TEENSY41") (pin "39-A15/CS/OUT1A") (pinfunction "39-A15/CS/OUT1A_39-A15/CS/OUT1A") (pintype "bidirectional"))
    )
    (net (code "68") (name "IO7_3V") (class "Default")
      (node (ref "JP6") (pin "8") (pinfunction "8_8") (pintype "passive"))
      (node (ref "R10") (pin "2") (pinfunction "2_2") (pintype "passive"))
      (node (ref "TEENSY41") (pin "40-A16/CS1") (pinfunction "40-A16/CS1_40-A16/CS1") (pintype "bidirectional"))
    )
    (net (code "69") (name "KICK") (class "Default")
      (node (ref "JP6") (pin "10") (pinfunction "10_10") (pintype "passive"))
      (node (ref "TEENSY41") (pin "14-A0/TX3/SPDIF_OUT") (pinfunction "14-A0/TX3/SPDIF_OUT_14-A0/TX3/SPDIF_OUT") (pintype "bidirectional"))
    )
    (net (code "70") (name "LED-") (class "Default")
      (node (ref "JP2") (pin "10") (pinfunction "10_10") (pintype "passive"))
      (node (ref "JP8") (pin "3") (pinfunction "3_3") (pintype "passive"))
    )
    (net (code "71") (name "MISO") (class "Default")
      (node (ref "JP8") (pin "24") (pinfunction "24_24") (pintype "passive"))
      (node (ref "TEENSY41") (pin "12-MISO/MQSL") (pinfunction "12-MISO/MQSL_12-MISO/MQSL") (pintype "bidirectional"))
    )
    (net (code "72") (name "MOSI") (class "Default")
      (node (ref "JP8") (pin "22") (pinfunction "22_22") (pintype "passive"))
      (node (ref "TEENSY41") (pin "11-MOSI/CTX1") (pinfunction "11-MOSI/CTX1_11-MOSI/CTX1") (pintype "bidirectional"))
    )
    (net (code "73") (name "MOT_A_A") (class "Default")
      (node (ref "DRIVER_A") (pin "OUTA") (pinfunction "OUTA_OUTA") (pintype "bidirectional"))
      (node (ref "DRIVER_A") (pin "OUTA_1") (pinfunction "OUTA_1_OUTA_1") (pintype "bidirectional"))
      (node (ref "JP3") (pin "1") (pinfunction "1_1") (pintype "passive"))
      (node (ref "JP3") (pin "3") (pinfunction "3_3") (pintype "passive"))
      (node (ref "JP3") (pin "5") (pinfunction "5_5") (pintype "passive"))
    )
    (net (code "74") (name "MOT_A_B") (class "Default")
      (node (ref "DRIVER_A") (pin "OUTB") (pinfunction "OUTB_OUTB") (pintype "bidirectional"))
      (node (ref "DRIVER_A") (pin "OUTB_1") (pinfunction "OUTB_1_OUTB_1") (pintype "bidirectional"))
      (node (ref "JP3") (pin "2") (pinfunction "2_2") (pintype "passive"))
      (node (ref "JP3") (pin "4") (pinfunction "4_4") (pintype "passive"))
      (node (ref "JP3") (pin "6") (pinfunction "6_6") (pintype "passive"))
    )
    (net (code "75") (name "MOT_B_A") (class "Default")
      (node (ref "DRIVER_B") (pin "OUTA") (pinfunction "OUTA_OUTA") (pintype "bidirectional"))
      (node (ref "DRIVER_B") (pin "OUTA_1") (pinfunction "OUTA_1_OUTA_1") (pintype "bidirectional"))
      (node (ref "JP7") (pin "1") (pinfunction "1_1") (pintype "passive"))
      (node (ref "JP7") (pin "3") (pinfunction "3_3") (pintype "passive"))
      (node (ref "JP7") (pin "5") (pinfunction "5_5") (pintype "passive"))
    )
    (net (code "76") (name "MOT_B_B") (class "Default")
      (node (ref "DRIVER_B") (pin "OUTB") (pinfunction "OUTB_OUTB") (pintype "bidirectional"))
      (node (ref "DRIVER_B") (pin "OUTB_1") (pinfunction "OUTB_1_OUTB_1") (pintype "bidirectional"))
      (node (ref "JP7") (pin "2") (pinfunction "2_2") (pintype "passive"))
      (node (ref "JP7") (pin "4") (pinfunction "4_4") (pintype "passive"))
      (node (ref "JP7") (pin "6") (pinfunction "6_6") (pintype "passive"))
    )
    (net (code "77") (name "MOT_C_A") (class "Default")
      (node (ref "DRIVER_C") (pin "OUTA") (pinfunction "OUTA_OUTA") (pintype "bidirectional"))
      (node (ref "DRIVER_C") (pin "OUTA_1") (pinfunction "OUTA_1_OUTA_1") (pintype "bidirectional"))
      (node (ref "JP5") (pin "1") (pinfunction "1_1") (pintype "passive"))
      (node (ref "JP5") (pin "3") (pinfunction "3_3") (pintype "passive"))
      (node (ref "JP5") (pin "5") (pinfunction "5_5") (pintype "passive"))
    )
    (net (code "78") (name "MOT_C_B") (class "Default")
      (node (ref "DRIVER_C") (pin "OUTB") (pinfunction "OUTB_OUTB") (pintype "bidirectional"))
      (node (ref "DRIVER_C") (pin "OUTB_1") (pinfunction "OUTB_1_OUTB_1") (pintype "bidirectional"))
      (node (ref "JP5") (pin "2") (pinfunction "2_2") (pintype "passive"))
      (node (ref "JP5") (pin "4") (pinfunction "4_4") (pintype "passive"))
      (node (ref "JP5") (pin "6") (pinfunction "6_6") (pintype "passive"))
    )
    (net (code "79") (name "MOT_D_A") (class "Default")
      (node (ref "DRIVER_D") (pin "OUTA") (pinfunction "OUTA_OUTA") (pintype "bidirectional"))
      (node (ref "DRIVER_D") (pin "OUTA_1") (pinfunction "OUTA_1_OUTA_1") (pintype "bidirectional"))
      (node (ref "JP4") (pin "1") (pinfunction "1_1") (pintype "passive"))
      (node (ref "JP4") (pin "3") (pinfunction "3_3") (pintype "passive"))
      (node (ref "JP4") (pin "5") (pinfunction "5_5") (pintype "passive"))
    )
    (net (code "80") (name "MOT_D_B") (class "Default")
      (node (ref "DRIVER_D") (pin "OUTB") (pinfunction "OUTB_OUTB") (pintype "bidirectional"))
      (node (ref "DRIVER_D") (pin "OUTB_1") (pinfunction "OUTB_1_OUTB_1") (pintype "bidirectional"))
      (node (ref "JP4") (pin "2") (pinfunction "2_2") (pintype "passive"))
      (node (ref "JP4") (pin "4") (pinfunction "4_4") (pintype "passive"))
      (node (ref "JP4") (pin "6") (pinfunction "6_6") (pintype "passive"))
    )
    (net (code "81") (name "Net-(INT-PadA)") (class "Default")
      (node (ref "INT") (pin "A") (pinfunction "A_A") (pintype "passive"))
      (node (ref "R11") (pin "1") (pinfunction "1_1") (pintype "passive"))
    )
    (net (code "82") (name "Net-(IO0-PadA)") (class "Default")
      (node (ref "IO0") (pin "A") (pinfunction "A_A") (pintype "passive"))
      (node (ref "R3") (pin "1") (pinfunction "1_1") (pintype "passive"))
    )
    (net (code "83") (name "Net-(IO1-PadA)") (class "Default")
      (node (ref "IO1") (pin "A") (pinfunction "A_A") (pintype "passive"))
      (node (ref "R4") (pin "1") (pinfunction "1_1") (pintype "passive"))
    )
    (net (code "84") (name "Net-(IO2-PadA)") (class "Default")
      (node (ref "IO2") (pin "A") (pinfunction "A_A") (pintype "passive"))
      (node (ref "R5") (pin "1") (pinfunction "1_1") (pintype "passive"))
    )
    (net (code "85") (name "Net-(IO3-PadA)") (class "Default")
      (node (ref "IO3") (pin "A") (pinfunction "A_A") (pintype "passive"))
      (node (ref "R6") (pin "1") (pinfunction "1_1") (pintype "passive"))
    )
    (net (code "86") (name "Net-(IO4-PadA)") (class "Default")
      (node (ref "IO4") (pin "A") (pinfunction "A_A") (pintype "passive"))
      (node (ref "R7") (pin "1") (pinfunction "1_1") (pintype "passive"))
    )
    (net (code "87") (name "Net-(IO5-PadA)") (class "Default")
      (node (ref "IO5") (pin "A") (pinfunction "A_A") (pintype "passive"))
      (node (ref "R8") (pin "1") (pinfunction "1_1") (pintype "passive"))
    )
    (net (code "88") (name "Net-(IO6-PadA)") (class "Default")
      (node (ref "IO6") (pin "A") (pinfunction "A_A") (pintype "passive"))
      (node (ref "R9") (pin "1") (pinfunction "1_1") (pintype "passive"))
    )
    (net (code "89") (name "Net-(IO7-PadA)") (class "Default")
      (node (ref "IO7") (pin "A") (pinfunction "A_A") (pintype "passive"))
      (node (ref "R10") (pin "1") (pinfunction "1_1") (pintype "passive"))
    )
    (net (code "90") (name "Net-(LM2596S-OUT)") (class "Default")
      (node (ref "L2") (pin "1") (pinfunction "1_1") (pintype "passive"))
      (node (ref "LM2596S") (pin "2") (pinfunction "OUT_2") (pintype "output"))
      (node (ref "Z1") (pin "C") (pinfunction "C_C") (pintype "passive"))
    )
    (net (code "91") (name "Net-(U2-AD0)") (class "Default")
      (node (ref "R12") (pin "1") (pinfunction "1_1") (pintype "passive"))
      (node (ref "U2") (pin "9") (pinfunction "AD0_9") (pintype "input"))
    )
    (net (code "92") (name "Net-(U2-CPOUT)") (class "Default")
      (node (ref "C14") (pin "1") (pinfunction "1_1") (pintype "passive"))
      (node (ref "U2") (pin "20") (pinfunction "CPOUT_20") (pintype "passive"))
    )
    (net (code "93") (name "Net-(U2-REGOUT)") (class "Default")
      (node (ref "C16") (pin "1") (pinfunction "1_1") (pintype "passive"))
      (node (ref "U2") (pin "10") (pinfunction "REGOUT_10") (pintype "passive"))
    )
    (net (code "94") (name "ON{slash}OFF") (class "Default")
      (node (ref "JP8") (pin "1") (pinfunction "1_1") (pintype "passive"))
      (node (ref "TEENSY41") (pin "ON/OFF") (pinfunction "ON/OFF_ON/OFF") (pintype "bidirectional"))
    )
    (net (code "95") (name "PWM_MOT_A") (class "Default")
      (node (ref "DRIVER_A") (pin "PWM") (pinfunction "PWM_PWM") (pintype "bidirectional"))
      (node (ref "TEENSY41") (pin "6-OUT1D") (pinfunction "6-OUT1D_6-OUT1D") (pintype "bidirectional"))
    )
    (net (code "96") (name "PWM_MOT_B") (class "Default")
      (node (ref "DRIVER_B") (pin "PWM") (pinfunction "PWM_PWM") (pintype "bidirectional"))
      (node (ref "TEENSY41") (pin "5-IN2") (pinfunction "5-IN2_5-IN2") (pintype "bidirectional"))
    )
    (net (code "97") (name "PWM_MOT_C") (class "Default")
      (node (ref "DRIVER_C") (pin "PWM") (pinfunction "PWM_PWM") (pintype "bidirectional"))
      (node (ref "TEENSY41") (pin "4-BCLK2") (pinfunction "4-BCLK2_4-BCLK2") (pintype "bidirectional"))
    )
    (net (code "98") (name "PWM_MOT_D") (class "Default")
      (node (ref "DRIVER_D") (pin "PWM") (pinfunction "PWM_PWM") (pintype "bidirectional"))
      (node (ref "TEENSY41") (pin "3-LRCLK2") (pinfunction "3-LRCLK2_3-LRCLK2") (pintype "bidirectional"))
    )
    (net (code "99") (name "PWR_BTN") (class "Default")
      (node (ref "JP2") (pin "1") (pinfunction "1_1") (pintype "passive"))
      (node (ref "JP8") (pin "11") (pinfunction "11_11") (pintype "passive"))
    )
    (net (code "100") (name "REF_MOTOR") (class "Default")
      (node (ref "C17") (pin "2") (pinfunction "2_2") (pintype "passive"))
      (node (ref "COMP_1") (pin "1") (pinfunction "1_1") (pintype "passive"))
      (node (ref "COMP_2") (pin "1") (pinfunction "1_1") (pintype "passive"))
      (node (ref "COMP_3") (pin "1") (pinfunction "1_1") (pintype "passive"))
      (node (ref "COMP_4") (pin "1") (pinfunction "1_1") (pintype "passive"))
      (node (ref "TRIM") (pin "2") (pinfunction "2_2") (pintype "passive"))
    )
    (net (code "101") (name "RXD{slash}D15") (class "Default")
      (node (ref "JP1") (pin "10") (pinfunction "10_10") (pintype "passive"))
      (node (ref "TEENSY41") (pin "29-TX7") (pinfunction "29-TX7_29-TX7") (pintype "bidirectional"))
    )
    (net (code "102") (name "SCK") (class "Default")
      (node (ref "JP8") (pin "26") (pinfunction "26_26") (pintype "passive"))
      (node (ref "TEENSY41") (pin "13-SCK/LED") (pinfunction "13-SCK/LED_13-SCK/LED") (pintype "bidirectional"))
    )
    (net (code "103") (name "SCL") (class "Default")
      (node (ref "JP11") (pin "6") (pinfunction "6_6") (pintype "passive"))
      (node (ref "JP12") (pin "6") (pinfunction "6_6") (pintype "passive"))
      (node (ref "JP8") (pin "19") (pinfunction "19_19") (pintype "passive"))
      (node (ref "R13") (pin "2") (pinfunction "2_2") (pintype "passive"))
      (node (ref "TEENSY41") (pin "19-A5/SCL0") (pinfunction "19-A5/SCL0_19-A5/SCL0") (pintype "bidirectional"))
      (node (ref "U2") (pin "23") (pinfunction "SCL_23") (pintype "input"))
    )
    (net (code "104") (name "SCL{slash}D3") (class "Default")
      (node (ref "JP1") (pin "5") (pinfunction "5_5") (pintype "passive"))
    )
    (net (code "105") (name "SDA") (class "Default")
      (node (ref "JP11") (pin "5") (pinfunction "5_5") (pintype "passive"))
      (node (ref "JP12") (pin "5") (pinfunction "5_5") (pintype "passive"))
      (node (ref "JP8") (pin "17") (pinfunction "17_17") (pintype "passive"))
      (node (ref "R14") (pin "2") (pinfunction "2_2") (pintype "passive"))
      (node (ref "TEENSY41") (pin "18-A4/SDA0") (pinfunction "18-A4/SDA0_18-A4/SDA0") (pintype "bidirectional"))
      (node (ref "U2") (pin "24") (pinfunction "SDA_24") (pintype "bidirectional"))
    )
    (net (code "106") (name "SDA{slash}D2") (class "Default")
      (node (ref "JP1") (pin "3") (pinfunction "3_3") (pintype "passive"))
    )
    (net (code "107") (name "SYS_RST") (class "Default")
      (node (ref "JP2") (pin "5") (pinfunction "5_5") (pintype "passive"))
      (node (ref "JP8") (pin "7") (pinfunction "7_7") (pintype "passive"))
    )
    (net (code "108") (name "TXD{slash}D14") (class "Default")
      (node (ref "JP1") (pin "8") (pinfunction "8_8") (pintype "passive"))
      (node (ref "TEENSY41") (pin "28-RX7") (pinfunction "28-RX7_28-RX7") (pintype "bidirectional"))
    )
    (net (code "109") (name "T_CS") (class "Default")
      (node (ref "JP8") (pin "21") (pinfunction "21_21") (pintype "passive"))
      (node (ref "TEENSY41") (pin "8-TX2/IN1") (pinfunction "8-TX2/IN1_8-TX2/IN1") (pintype "bidirectional"))
    )
    (net (code "110") (name "T_IRQ") (class "Default")
      (node (ref "JP8") (pin "23") (pinfunction "23_23") (pintype "passive"))
      (node (ref "TEENSY41") (pin "2-OUT2") (pinfunction "2-OUT2_2-OUT2") (pintype "bidirectional"))
    )
    (net (code "111") (name "UART_RXD") (class "Default")
      (node (ref "JP2") (pin "9") (pinfunction "9_9") (pintype "passive"))
    )
    (net (code "112") (name "UART_TXD") (class "Default")
      (node (ref "JP2") (pin "8") (pinfunction "8_8") (pintype "passive"))
    )
    (net (code "113") (name "V_BAT") (class "Default")
      (node (ref "R1") (pin "2") (pinfunction "2_2") (pintype "passive"))
      (node (ref "R2") (pin "1") (pinfunction "1_1") (pintype "passive"))
      (node (ref "TEENSY41") (pin "16-A2/RX4/SCL1") (pinfunction "16-A2/RX4/SCL1_16-A2/RX4/SCL1") (pintype "bidirectional"))
    )
    (net (code "114") (name "V_CAP") (class "Default")
      (node (ref "JP6") (pin "12") (pinfunction "12_12") (pintype "passive"))
      (node (ref "TEENSY41") (pin "17-A3/TX4/SDA1") (pinfunction "17-A3/TX4/SDA1_17-A3/TX4/SDA1") (pintype "bidirectional"))
    )
    (net (code "115") (name "unconnected-(DRIVER_A-PadENA{slash}DIAGA)") (class "Default")
      (node (ref "DRIVER_A") (pin "ENA/DIAGA") (pinfunction "ENA/DIAGA_ENA/DIAGA") (pintype "bidirectional"))
    )
    (net (code "116") (name "unconnected-(DRIVER_A-PadENB{slash}DIAGB)") (class "Default")
      (node (ref "DRIVER_A") (pin "ENB/DIAGB") (pinfunction "ENB/DIAGB_ENB/DIAGB") (pintype "bidirectional"))
    )
    (net (code "117") (name "unconnected-(DRIVER_A-PadVOUT)") (class "Default")
      (node (ref "DRIVER_A") (pin "VOUT") (pinfunction "VOUT_VOUT") (pintype "bidirectional"))
    )
    (net (code "118") (name "unconnected-(DRIVER_B-PadENA{slash}DIAGA)") (class "Default")
      (node (ref "DRIVER_B") (pin "ENA/DIAGA") (pinfunction "ENA/DIAGA_ENA/DIAGA") (pintype "bidirectional"))
    )
    (net (code "119") (name "unconnected-(DRIVER_B-PadENB{slash}DIAGB)") (class "Default")
      (node (ref "DRIVER_B") (pin "ENB/DIAGB") (pinfunction "ENB/DIAGB_ENB/DIAGB") (pintype "bidirectional"))
    )
    (net (code "120") (name "unconnected-(DRIVER_B-PadVOUT)") (class "Default")
      (node (ref "DRIVER_B") (pin "VOUT") (pinfunction "VOUT_VOUT") (pintype "bidirectional"))
    )
    (net (code "121") (name "unconnected-(DRIVER_C-PadENA{slash}DIAGA)") (class "Default")
      (node (ref "DRIVER_C") (pin "ENA/DIAGA") (pinfunction "ENA/DIAGA_ENA/DIAGA") (pintype "bidirectional"))
    )
    (net (code "122") (name "unconnected-(DRIVER_C-PadENB{slash}DIAGB)") (class "Default")
      (node (ref "DRIVER_C") (pin "ENB/DIAGB") (pinfunction "ENB/DIAGB_ENB/DIAGB") (pintype "bidirectional"))
    )
    (net (code "123") (name "unconnected-(DRIVER_C-PadVOUT)") (class "Default")
      (node (ref "DRIVER_C") (pin "VOUT") (pinfunction "VOUT_VOUT") (pintype "bidirectional"))
    )
    (net (code "124") (name "unconnected-(DRIVER_D-PadENA{slash}DIAGA)") (class "Default")
      (node (ref "DRIVER_D") (pin "ENA/DIAGA") (pinfunction "ENA/DIAGA_ENA/DIAGA") (pintype "bidirectional"))
    )
    (net (code "125") (name "unconnected-(DRIVER_D-PadENB{slash}DIAGB)") (class "Default")
      (node (ref "DRIVER_D") (pin "ENB/DIAGB") (pinfunction "ENB/DIAGB_ENB/DIAGB") (pintype "bidirectional"))
    )
    (net (code "126") (name "unconnected-(DRIVER_D-PadVOUT)") (class "Default")
      (node (ref "DRIVER_D") (pin "VOUT") (pinfunction "VOUT_VOUT") (pintype "bidirectional"))
    )
    (net (code "127") (name "unconnected-(MAIN_POWER-3-ON-Pad3)") (class "Default")
      (node (ref "MAIN_POWER") (pin "3") (pinfunction "3-ON_3") (pintype "passive"))
    )
    (net (code "128") (name "unconnected-(OR_1-A4-Pad12)") (class "Default")
      (node (ref "OR_1") (pin "12") (pinfunction "A4_12") (pintype "input"))
    )
    (net (code "129") (name "unconnected-(OR_1-B4-Pad13)") (class "Default")
      (node (ref "OR_1") (pin "13") (pinfunction "B4_13") (pintype "input"))
    )
    (net (code "130") (name "unconnected-(OR_1-Y4-Pad11)") (class "Default")
      (node (ref "OR_1") (pin "11") (pinfunction "Y4_11") (pintype "output"))
    )
    (net (code "131") (name "unconnected-(TEENSY41-Pad3V3-1)") (class "Default")
      (node (ref "TEENSY41") (pin "3V3-1") (pinfunction "3V3-1_3V3-1") (pintype "bidirectional"))
    )
    (net (code "132") (name "unconnected-(TEENSY41-Pad3V3-2)") (class "Default")
      (node (ref "TEENSY41") (pin "3V3-2") (pinfunction "3V3-2_3V3-2") (pintype "bidirectional"))
    )
    (net (code "133") (name "unconnected-(TEENSY41-Pad3V3-3)") (class "Default")
      (node (ref "TEENSY41") (pin "3V3-3") (pinfunction "3V3-3_3V3-3") (pintype "bidirectional"))
    )
    (net (code "134") (name "unconnected-(TEENSY41-PadDM)") (class "Default")
      (node (ref "TEENSY41") (pin "DM") (pinfunction "DM_DM") (pintype "bidirectional"))
    )
    (net (code "135") (name "unconnected-(TEENSY41-PadDP)") (class "Default")
      (node (ref "TEENSY41") (pin "DP") (pinfunction "DP_DP") (pintype "bidirectional"))
    )
    (net (code "136") (name "unconnected-(TEENSY41-PadPROGRAM)") (class "Default")
      (node (ref "TEENSY41") (pin "PROGRAM") (pinfunction "PROGRAM_PROGRAM") (pintype "bidirectional"))
    )
    (net (code "137") (name "unconnected-(TEENSY41-PadVBAT)") (class "Default")
      (node (ref "TEENSY41") (pin "VBAT") (pinfunction "VBAT_VBAT") (pintype "bidirectional"))
    )
    (net (code "138") (name "unconnected-(TEENSY41-PadVUSB)") (class "Default")
      (node (ref "TEENSY41") (pin "VUSB") (pinfunction "VUSB_VUSB") (pintype "bidirectional"))
    )
    (net (code "139") (name "unconnected-(U2-AUX_CL-Pad7)") (class "Default")
      (node (ref "U2") (pin "7") (pinfunction "AUX_CL_7") (pintype "input"))
    )
    (net (code "140") (name "unconnected-(U2-AUX_DA-Pad6)") (class "Default")
      (node (ref "U2") (pin "6") (pinfunction "AUX_DA_6") (pintype "bidirectional"))
    )
    (net (code "141") (name "unconnected-(U2-INT-Pad12)") (class "Default")
      (node (ref "U2") (pin "12") (pinfunction "INT_12") (pintype "output"))
    )
    (net (code "142") (name "unconnected-(U2-RESV-Pad19)") (class "Default")
      (node (ref "U2") (pin "19") (pinfunction "RESV_19") (pintype "passive"))
    )
    (net (code "143") (name "unconnected-(U2-RESV-Pad21)") (class "Default")
      (node (ref "U2") (pin "21") (pinfunction "RESV_21") (pintype "passive"))
    )
    (net (code "144") (name "unconnected-(U2-RESV-Pad22)") (class "Default")
      (node (ref "U2") (pin "22") (pinfunction "RESV_22") (pintype "passive"))
    )
  )
)
